# RP_ComputeModule3_rev_3_0_Displays.net
KiCad netlist of a schematic drawn in Altium Designer
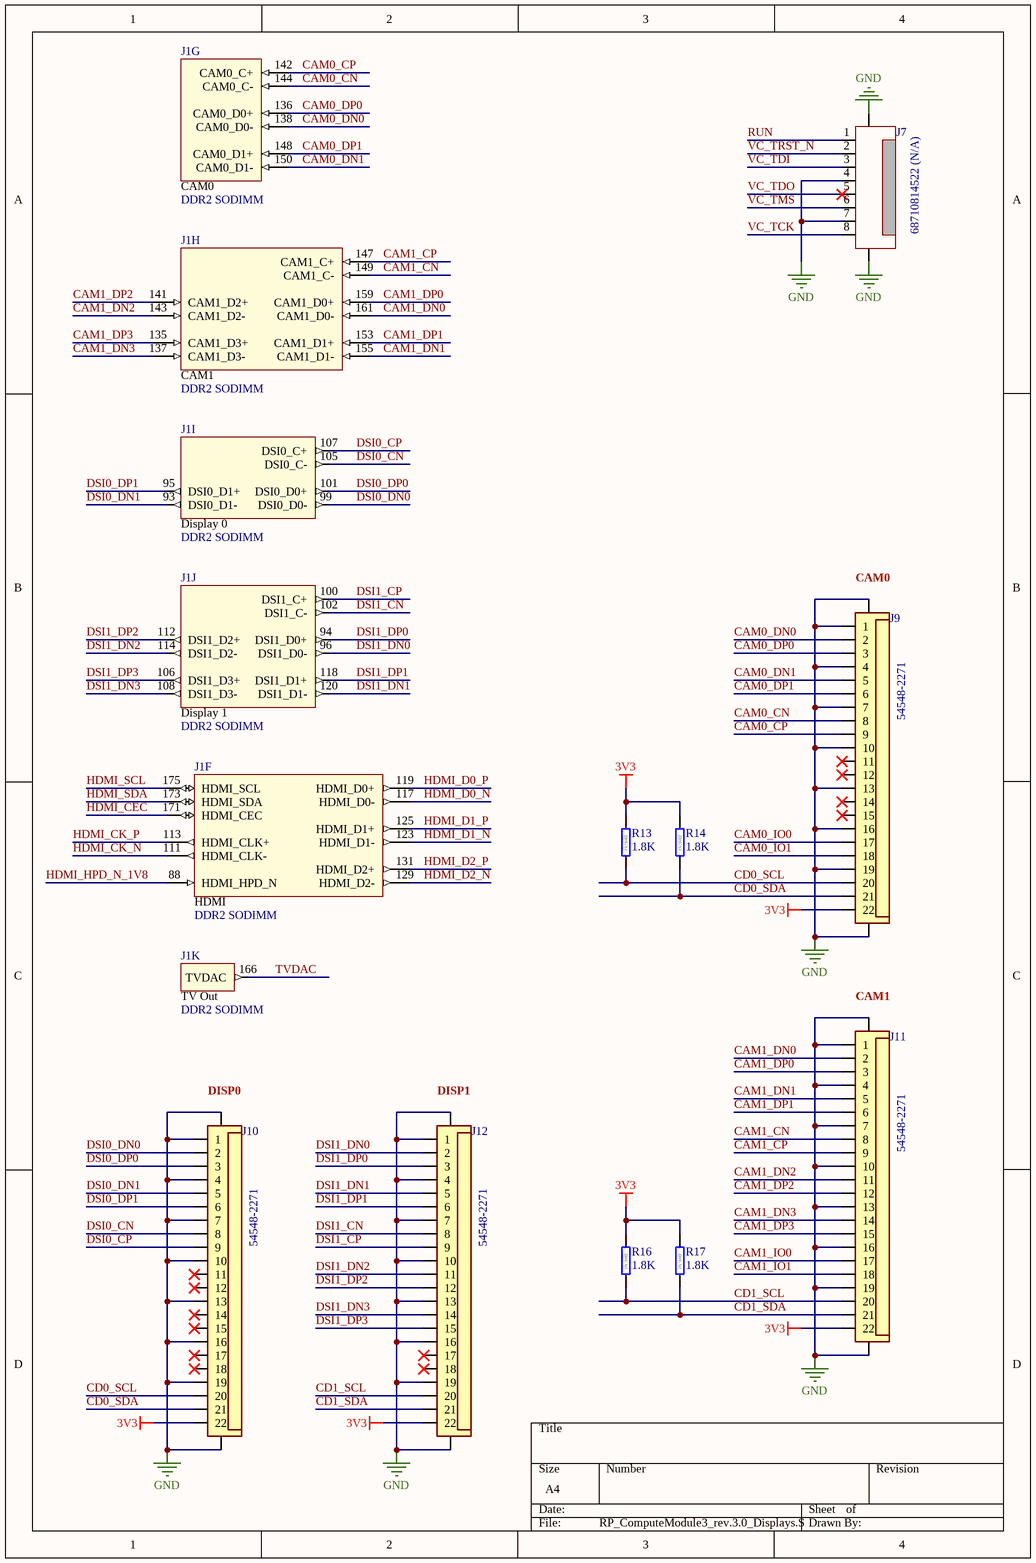
[diagram p0: RP_ComputeModule3_rev.3.0_Displays.SchDoc]

(export (version "E")
  (design (tool "Eeschema 10.0.6"))
  (components
    (comp (ref "J1")
      (value "DDR2 SODIMM")
      (footprint "TE 1473005-4 (DDR2 SO-DIMM)")
      (description "TE CONNECTIVITY / AMP         1473005-4             SOCKET IC, DIMM, DDR2, 1.8V, 200WAY")
      (fields
        (field (name "MANUFACTURER") "TE Connectivity")
        (field (name "MANUFACTURER PART NUMBER") "1473005-4")
      )
      (libsource (lib "TEConnectivity_AMP") (part "1473005-4"))
    )
    (comp (ref "J7")
      (value "68710814522 (N/A)")
      (footprint "WE 68710814522 N/A")
      (description "CONN FPC BOTTOM 8POS 0.50MM R/A")
      (fields
        (field (name "MANUFACTURER") "Wurth Electronics")
        (field (name "MANUFACTURER PART NUMBER") "68710814522")
      )
      (libsource (lib "WE_Library") (part "68710814522_N/A"))
    )
    (comp (ref "J9")
      (value "54548-2271")
      (footprint "Molex 54548-2271")
      (description "Conn FFC/FPC Connector SKT 22 POS 0.5mm Solder RA SMD Easy-On™ T/R")
      (fields (field (name "MANUFACTURER") "Molex") (field (name "MANUFACTURER PART NUMBER") "0545482271"))
      (libsource (lib "Molex_Library") (part "0545482271"))
    )
    (comp (ref "J10")
      (value "54548-2271")
      (footprint "Molex 54548-2271")
      (description "Conn FFC/FPC Connector SKT 22 POS 0.5mm Solder RA SMD Easy-On™ T/R")
      (fields (field (name "MANUFACTURER") "Molex") (field (name "MANUFACTURER PART NUMBER") "0545482271"))
      (libsource (lib "Molex_Library") (part "0545482271"))
    )
    (comp (ref "J11")
      (value "54548-2271")
      (footprint "Molex 54548-2271")
      (description "Conn FFC/FPC Connector SKT 22 POS 0.5mm Solder RA SMD Easy-On™ T/R")
      (fields (field (name "MANUFACTURER") "Molex") (field (name "MANUFACTURER PART NUMBER") "0545482271"))
      (libsource (lib "Molex_Library") (part "0545482271"))
    )
    (comp (ref "J12")
      (value "54548-2271")
      (footprint "Molex 54548-2271")
      (description "Conn FFC/FPC Connector SKT 22 POS 0.5mm Solder RA SMD Easy-On™ T/R")
      (fields (field (name "MANUFACTURER") "Molex") (field (name "MANUFACTURER PART NUMBER") "0545482271"))
      (libsource (lib "Molex_Library") (part "0545482271"))
    )
    (comp (ref "R13")
      (value "1.8K")
      (footprint "RES0402")
      (description "Thick Film Resistors - SMD 1.8K OHM 1%")
      (fields
        (field (name "MANUFACTURER") "KOA Speer")
        (field (name "MANUFACTURER PART NUMBER") "RK73H1ETTP1801F")
      )
      (libsource (lib "KOA_Resistors") (part "RK73H1ETTP1801F"))
    )
    (comp (ref "R14")
      (value "1.8K")
      (footprint "RES0402")
      (description "Thick Film Resistors - SMD 1.8K OHM 1%")
      (fields
        (field (name "MANUFACTURER") "KOA Speer")
        (field (name "MANUFACTURER PART NUMBER") "RK73H1ETTP1801F")
      )
      (libsource (lib "KOA_Resistors") (part "RK73H1ETTP1801F"))
    )
    (comp (ref "R16")
      (value "1.8K")
      (footprint "RES0402")
      (description "Thick Film Resistors - SMD 1.8K OHM 1%")
      (fields
        (field (name "MANUFACTURER") "KOA Speer")
        (field (name "MANUFACTURER PART NUMBER") "RK73H1ETTP1801F")
      )
      (libsource (lib "KOA_Resistors") (part "RK73H1ETTP1801F"))
    )
    (comp (ref "R17")
      (value "1.8K")
      (footprint "RES0402")
      (description "Thick Film Resistors - SMD 1.8K OHM 1%")
      (fields
        (field (name "MANUFACTURER") "KOA Speer")
        (field (name "MANUFACTURER PART NUMBER") "RK73H1ETTP1801F")
      )
      (libsource (lib "KOA_Resistors") (part "RK73H1ETTP1801F"))
    )
  )
  (nets
    (net (code "1") (name "/CAM0_CN") (class "Default")
      (node (ref "J1") (pin "144") (pinfunction "CAM0_C-_144") (pintype "input"))
      (node (ref "J9") (pin "8") (pinfunction "8_8") (pintype "passive"))
    )
    (net (code "2") (name "/CAM0_CP") (class "Default")
      (node (ref "J1") (pin "142") (pinfunction "CAM0_C+_142") (pintype "input"))
      (node (ref "J9") (pin "9") (pinfunction "9_9") (pintype "passive"))
    )
    (net (code "3") (name "/CAM0_DN0") (class "Default")
      (node (ref "J1") (pin "138") (pinfunction "CAM0_D0-_138") (pintype "input"))
      (node (ref "J9") (pin "2") (pinfunction "2_2") (pintype "passive"))
    )
    (net (code "4") (name "/CAM0_DN1") (class "Default")
      (node (ref "J1") (pin "150") (pinfunction "CAM0_D1-_150") (pintype "input"))
      (node (ref "J9") (pin "5") (pinfunction "5_5") (pintype "passive"))
    )
    (net (code "5") (name "/CAM0_DP0") (class "Default")
      (node (ref "J1") (pin "136") (pinfunction "CAM0_D0+_136") (pintype "input"))
      (node (ref "J9") (pin "3") (pinfunction "3_3") (pintype "passive"))
    )
    (net (code "6") (name "/CAM0_DP1") (class "Default")
      (node (ref "J1") (pin "148") (pinfunction "CAM0_D1+_148") (pintype "input"))
      (node (ref "J9") (pin "6") (pinfunction "6_6") (pintype "passive"))
    )
    (net (code "7") (name "/CAM0_IO0") (class "Default")
      (node (ref "J9") (pin "17") (pinfunction "17_17") (pintype "passive"))
    )
    (net (code "8") (name "/CAM0_IO1") (class "Default")
      (node (ref "J9") (pin "18") (pinfunction "18_18") (pintype "passive"))
    )
    (net (code "9") (name "/CAM1_CN") (class "Default")
      (node (ref "J1") (pin "149") (pinfunction "CAM1_C-_149") (pintype "input"))
      (node (ref "J11") (pin "8") (pinfunction "8_8") (pintype "passive"))
    )
    (net (code "10") (name "/CAM1_CP") (class "Default")
      (node (ref "J1") (pin "147") (pinfunction "CAM1_C+_147") (pintype "input"))
      (node (ref "J11") (pin "9") (pinfunction "9_9") (pintype "passive"))
    )
    (net (code "11") (name "/CAM1_DN0") (class "Default")
      (node (ref "J1") (pin "161") (pinfunction "CAM1_D0-_161") (pintype "input"))
      (node (ref "J11") (pin "2") (pinfunction "2_2") (pintype "passive"))
    )
    (net (code "12") (name "/CAM1_DN1") (class "Default")
      (node (ref "J1") (pin "155") (pinfunction "CAM1_D1-_155") (pintype "input"))
      (node (ref "J11") (pin "5") (pinfunction "5_5") (pintype "passive"))
    )
    (net (code "13") (name "/CAM1_DN2") (class "Default")
      (node (ref "J1") (pin "143") (pinfunction "CAM1_D2-_143") (pintype "input"))
      (node (ref "J11") (pin "11") (pinfunction "11_11") (pintype "passive"))
    )
    (net (code "14") (name "/CAM1_DN3") (class "Default")
      (node (ref "J1") (pin "137") (pinfunction "CAM1_D3-_137") (pintype "input"))
      (node (ref "J11") (pin "14") (pinfunction "14_14") (pintype "passive"))
    )
    (net (code "15") (name "/CAM1_DP0") (class "Default")
      (node (ref "J1") (pin "159") (pinfunction "CAM1_D0+_159") (pintype "input"))
      (node (ref "J11") (pin "3") (pinfunction "3_3") (pintype "passive"))
    )
    (net (code "16") (name "/CAM1_DP1") (class "Default")
      (node (ref "J1") (pin "153") (pinfunction "CAM1_D1+_153") (pintype "input"))
      (node (ref "J11") (pin "6") (pinfunction "6_6") (pintype "passive"))
    )
    (net (code "17") (name "/CAM1_DP2") (class "Default")
      (node (ref "J1") (pin "141") (pinfunction "CAM1_D2+_141") (pintype "input"))
      (node (ref "J11") (pin "12") (pinfunction "12_12") (pintype "passive"))
    )
    (net (code "18") (name "/CAM1_DP3") (class "Default")
      (node (ref "J1") (pin "135") (pinfunction "CAM1_D3+_135") (pintype "input"))
      (node (ref "J11") (pin "15") (pinfunction "15_15") (pintype "passive"))
    )
    (net (code "19") (name "/CAM1_IO0") (class "Default")
      (node (ref "J11") (pin "17") (pinfunction "17_17") (pintype "passive"))
    )
    (net (code "20") (name "/CAM1_IO1") (class "Default")
      (node (ref "J11") (pin "18") (pinfunction "18_18") (pintype "passive"))
    )
    (net (code "21") (name "/CD0_SCL") (class "Default")
      (node (ref "J10") (pin "20") (pinfunction "20_20") (pintype "passive"))
      (node (ref "J9") (pin "20") (pinfunction "20_20") (pintype "passive"))
      (node (ref "R13") (pin "2") (pinfunction "2_2") (pintype "passive"))
    )
    (net (code "22") (name "/CD0_SDA") (class "Default")
      (node (ref "J10") (pin "21") (pinfunction "21_21") (pintype "passive"))
      (node (ref "J9") (pin "21") (pinfunction "21_21") (pintype "passive"))
      (node (ref "R14") (pin "2") (pinfunction "2_2") (pintype "passive"))
    )
    (net (code "23") (name "/CD1_SCL") (class "Default")
      (node (ref "J11") (pin "20") (pinfunction "20_20") (pintype "passive"))
      (node (ref "J12") (pin "20") (pinfunction "20_20") (pintype "passive"))
      (node (ref "R16") (pin "2") (pinfunction "2_2") (pintype "passive"))
    )
    (net (code "24") (name "/CD1_SDA") (class "Default")
      (node (ref "J11") (pin "21") (pinfunction "21_21") (pintype "passive"))
      (node (ref "J12") (pin "21") (pinfunction "21_21") (pintype "passive"))
      (node (ref "R17") (pin "2") (pinfunction "2_2") (pintype "passive"))
    )
    (net (code "25") (name "/DSI0_CN") (class "Default")
      (node (ref "J1") (pin "105") (pinfunction "DSI0_C-_105") (pintype "output"))
      (node (ref "J10") (pin "8") (pinfunction "8_8") (pintype "passive"))
    )
    (net (code "26") (name "/DSI0_CP") (class "Default")
      (node (ref "J1") (pin "107") (pinfunction "DSI0_C+_107") (pintype "output"))
      (node (ref "J10") (pin "9") (pinfunction "9_9") (pintype "passive"))
    )
    (net (code "27") (name "/DSI0_DN0") (class "Default")
      (node (ref "J1") (pin "99") (pinfunction "DSI0_D0-_99") (pintype "output"))
      (node (ref "J10") (pin "2") (pinfunction "2_2") (pintype "passive"))
    )
    (net (code "28") (name "/DSI0_DN1") (class "Default")
      (node (ref "J1") (pin "93") (pinfunction "DSI0_D1-_93") (pintype "output"))
      (node (ref "J10") (pin "5") (pinfunction "5_5") (pintype "passive"))
    )
    (net (code "29") (name "/DSI0_DP0") (class "Default")
      (node (ref "J1") (pin "101") (pinfunction "DSI0_D0+_101") (pintype "output"))
      (node (ref "J10") (pin "3") (pinfunction "3_3") (pintype "passive"))
    )
    (net (code "30") (name "/DSI0_DP1") (class "Default")
      (node (ref "J1") (pin "95") (pinfunction "DSI0_D1+_95") (pintype "output"))
      (node (ref "J10") (pin "6") (pinfunction "6_6") (pintype "passive"))
    )
    (net (code "31") (name "/DSI1_CN") (class "Default")
      (node (ref "J1") (pin "102") (pinfunction "DSI1_C-_102") (pintype "output"))
      (node (ref "J12") (pin "8") (pinfunction "8_8") (pintype "passive"))
    )
    (net (code "32") (name "/DSI1_CP") (class "Default")
      (node (ref "J1") (pin "100") (pinfunction "DSI1_C+_100") (pintype "output"))
      (node (ref "J12") (pin "9") (pinfunction "9_9") (pintype "passive"))
    )
    (net (code "33") (name "/DSI1_DN0") (class "Default")
      (node (ref "J1") (pin "96") (pinfunction "DSI1_D0-_96") (pintype "output"))
      (node (ref "J12") (pin "2") (pinfunction "2_2") (pintype "passive"))
    )
    (net (code "34") (name "/DSI1_DN1") (class "Default")
      (node (ref "J1") (pin "120") (pinfunction "DSI1_D1-_120") (pintype "output"))
      (node (ref "J12") (pin "5") (pinfunction "5_5") (pintype "passive"))
    )
    (net (code "35") (name "/DSI1_DN2") (class "Default")
      (node (ref "J1") (pin "114") (pinfunction "DSI1_D2-_114") (pintype "output"))
      (node (ref "J12") (pin "11") (pinfunction "11_11") (pintype "passive"))
    )
    (net (code "36") (name "/DSI1_DN3") (class "Default")
      (node (ref "J1") (pin "108") (pinfunction "DSI1_D3-_108") (pintype "output"))
      (node (ref "J12") (pin "14") (pinfunction "14_14") (pintype "passive"))
    )
    (net (code "37") (name "/DSI1_DP0") (class "Default")
      (node (ref "J1") (pin "94") (pinfunction "DSI1_D0+_94") (pintype "output"))
      (node (ref "J12") (pin "3") (pinfunction "3_3") (pintype "passive"))
    )
    (net (code "38") (name "/DSI1_DP1") (class "Default")
      (node (ref "J1") (pin "118") (pinfunction "DSI1_D1+_118") (pintype "output"))
      (node (ref "J12") (pin "6") (pinfunction "6_6") (pintype "passive"))
    )
    (net (code "39") (name "/DSI1_DP2") (class "Default")
      (node (ref "J1") (pin "112") (pinfunction "DSI1_D2+_112") (pintype "output"))
      (node (ref "J12") (pin "12") (pinfunction "12_12") (pintype "passive"))
    )
    (net (code "40") (name "/DSI1_DP3") (class "Default")
      (node (ref "J1") (pin "106") (pinfunction "DSI1_D3+_106") (pintype "output"))
      (node (ref "J12") (pin "15") (pinfunction "15_15") (pintype "passive"))
    )
    (net (code "41") (name "/HDMI_CEC") (class "Default")
      (node (ref "J1") (pin "171") (pinfunction "HDMI_CEC_171") (pintype "bidirectional"))
    )
    (net (code "42") (name "/HDMI_CK_N") (class "Default")
      (node (ref "J1") (pin "111") (pinfunction "HDMI_CLK-_111") (pintype "output"))
    )
    (net (code "43") (name "/HDMI_CK_P") (class "Default")
      (node (ref "J1") (pin "113") (pinfunction "HDMI_CLK+_113") (pintype "output"))
    )
    (net (code "44") (name "/HDMI_D0_N") (class "Default")
      (node (ref "J1") (pin "117") (pinfunction "HDMI_D0-_117") (pintype "output"))
    )
    (net (code "45") (name "/HDMI_D0_P") (class "Default")
      (node (ref "J1") (pin "119") (pinfunction "HDMI_D0+_119") (pintype "output"))
    )
    (net (code "46") (name "/HDMI_D1_N") (class "Default")
      (node (ref "J1") (pin "123") (pinfunction "HDMI_D1-_123") (pintype "output"))
    )
    (net (code "47") (name "/HDMI_D1_P") (class "Default")
      (node (ref "J1") (pin "125") (pinfunction "HDMI_D1+_125") (pintype "output"))
    )
    (net (code "48") (name "/HDMI_D2_N") (class "Default")
      (node (ref "J1") (pin "129") (pinfunction "HDMI_D2-_129") (pintype "output"))
    )
    (net (code "49") (name "/HDMI_D2_P") (class "Default")
      (node (ref "J1") (pin "131") (pinfunction "HDMI_D2+_131") (pintype "output"))
    )
    (net (code "50") (name "/HDMI_HPD_N_1V8") (class "Default")
      (node (ref "J1") (pin "88") (pinfunction "HDMI_HPD_N_88") (pintype "input"))
    )
    (net (code "51") (name "/HDMI_SCL") (class "Default")
      (node (ref "J1") (pin "175") (pinfunction "HDMI_SCL_175") (pintype "bidirectional"))
    )
    (net (code "52") (name "/HDMI_SDA") (class "Default")
      (node (ref "J1") (pin "173") (pinfunction "HDMI_SDA_173") (pintype "bidirectional"))
    )
    (net (code "53") (name "/RUN") (class "Default")
      (node (ref "J7") (pin "1") (pinfunction "1_1") (pintype "passive"))
    )
    (net (code "54") (name "/TVDAC") (class "Default")
      (node (ref "J1") (pin "166") (pinfunction "TVDAC_166") (pintype "output"))
    )
    (net (code "55") (name "/VC_TCK") (class "Default")
      (node (ref "J7") (pin "8") (pinfunction "8_8") (pintype "passive"))
    )
    (net (code "56") (name "/VC_TDI") (class "Default")
      (node (ref "J7") (pin "3") (pinfunction "3_3") (pintype "passive"))
    )
    (net (code "57") (name "/VC_TDO") (class "Default")
      (node (ref "J7") (pin "5") (pinfunction "5_5") (pintype "passive+no_connect"))
    )
    (net (code "58") (name "/VC_TMS") (class "Default")
      (node (ref "J7") (pin "6") (pinfunction "6_6") (pintype "passive"))
    )
    (net (code "59") (name "/VC_TRST_N") (class "Default")
      (node (ref "J7") (pin "2") (pinfunction "2_2") (pintype "passive"))
    )
    (net (code "60") (name "3V3") (class "Default")
      (node (ref "J10") (pin "22") (pinfunction "22_22") (pintype "passive"))
      (node (ref "J11") (pin "22") (pinfunction "22_22") (pintype "passive"))
      (node (ref "J12") (pin "22") (pinfunction "22_22") (pintype "passive"))
      (node (ref "J9") (pin "22") (pinfunction "22_22") (pintype "passive"))
      (node (ref "R13") (pin "1") (pinfunction "1_1") (pintype "passive"))
      (node (ref "R14") (pin "1") (pinfunction "1_1") (pintype "passive"))
      (node (ref "R16") (pin "1") (pinfunction "1_1") (pintype "passive"))
      (node (ref "R17") (pin "1") (pinfunction "1_1") (pintype "passive"))
    )
    (net (code "61") (name "GND") (class "Default")
      (node (ref "J10") (pin "1") (pinfunction "1_1") (pintype "passive"))
      (node (ref "J10") (pin "10") (pinfunction "10_10") (pintype "passive"))
      (node (ref "J10") (pin "13") (pinfunction "13_13") (pintype "passive"))
      (node (ref "J10") (pin "16") (pinfunction "16_16") (pintype "passive"))
      (node (ref "J10") (pin "19") (pinfunction "19_19") (pintype "passive"))
      (node (ref "J10") (pin "4") (pinfunction "4_4") (pintype "passive"))
      (node (ref "J10") (pin "7") (pinfunction "7_7") (pintype "passive"))
      (node (ref "J10") (pin "G1") (pinfunction "G1_G1") (pintype "passive"))
      (node (ref "J10") (pin "G2") (pinfunction "G2_G2") (pintype "passive"))
      (node (ref "J11") (pin "1") (pinfunction "1_1") (pintype "passive"))
      (node (ref "J11") (pin "10") (pinfunction "10_10") (pintype "passive"))
      (node (ref "J11") (pin "13") (pinfunction "13_13") (pintype "passive"))
      (node (ref "J11") (pin "16") (pinfunction "16_16") (pintype "passive"))
      (node (ref "J11") (pin "19") (pinfunction "19_19") (pintype "passive"))
      (node (ref "J11") (pin "4") (pinfunction "4_4") (pintype "passive"))
      (node (ref "J11") (pin "7") (pinfunction "7_7") (pintype "passive"))
      (node (ref "J11") (pin "G1") (pinfunction "G1_G1") (pintype "passive"))
      (node (ref "J11") (pin "G2") (pinfunction "G2_G2") (pintype "passive"))
      (node (ref "J12") (pin "1") (pinfunction "1_1") (pintype "passive"))
      (node (ref "J12") (pin "10") (pinfunction "10_10") (pintype "passive"))
      (node (ref "J12") (pin "13") (pinfunction "13_13") (pintype "passive"))
      (node (ref "J12") (pin "16") (pinfunction "16_16") (pintype "passive"))
      (node (ref "J12") (pin "19") (pinfunction "19_19") (pintype "passive"))
      (node (ref "J12") (pin "4") (pinfunction "4_4") (pintype "passive"))
      (node (ref "J12") (pin "7") (pinfunction "7_7") (pintype "passive"))
      (node (ref "J12") (pin "G1") (pinfunction "G1_G1") (pintype "passive"))
      (node (ref "J12") (pin "G2") (pinfunction "G2_G2") (pintype "passive"))
      (node (ref "J7") (pin "10") (pinfunction "10_10") (pintype "passive"))
      (node (ref "J7") (pin "4") (pinfunction "4_4") (pintype "passive"))
      (node (ref "J7") (pin "7") (pinfunction "7_7") (pintype "passive"))
      (node (ref "J7") (pin "9") (pinfunction "9_9") (pintype "passive"))
      (node (ref "J9") (pin "1") (pinfunction "1_1") (pintype "passive"))
      (node (ref "J9") (pin "10") (pinfunction "10_10") (pintype "passive"))
      (node (ref "J9") (pin "13") (pinfunction "13_13") (pintype "passive"))
      (node (ref "J9") (pin "16") (pinfunction "16_16") (pintype "passive"))
      (node (ref "J9") (pin "19") (pinfunction "19_19") (pintype "passive"))
      (node (ref "J9") (pin "4") (pinfunction "4_4") (pintype "passive"))
      (node (ref "J9") (pin "7") (pinfunction "7_7") (pintype "passive"))
      (node (ref "J9") (pin "G1") (pinfunction "G1_G1") (pintype "passive"))
      (node (ref "J9") (pin "G2") (pinfunction "G2_G2") (pintype "passive"))
    )
    (net (code "62") (name "unconnected-(J9-Pad11)") (class "Default")
      (node (ref "J9") (pin "11") (pinfunction "11_11") (pintype "passive+no_connect"))
    )
    (net (code "63") (name "unconnected-(J9-Pad12)") (class "Default")
      (node (ref "J9") (pin "12") (pinfunction "12_12") (pintype "passive+no_connect"))
    )
    (net (code "64") (name "unconnected-(J9-Pad14)") (class "Default")
      (node (ref "J9") (pin "14") (pinfunction "14_14") (pintype "passive+no_connect"))
    )
    (net (code "65") (name "unconnected-(J9-Pad15)") (class "Default")
      (node (ref "J9") (pin "15") (pinfunction "15_15") (pintype "passive+no_connect"))
    )
    (net (code "66") (name "unconnected-(J10-Pad11)") (class "Default")
      (node (ref "J10") (pin "11") (pinfunction "11_11") (pintype "passive+no_connect"))
    )
    (net (code "67") (name "unconnected-(J10-Pad12)") (class "Default")
      (node (ref "J10") (pin "12") (pinfunction "12_12") (pintype "passive+no_connect"))
    )
    (net (code "68") (name "unconnected-(J10-Pad14)") (class "Default")
      (node (ref "J10") (pin "14") (pinfunction "14_14") (pintype "passive+no_connect"))
    )
    (net (code "69") (name "unconnected-(J10-Pad15)") (class "Default")
      (node (ref "J10") (pin "15") (pinfunction "15_15") (pintype "passive+no_connect"))
    )
    (net (code "70") (name "unconnected-(J10-Pad17)") (class "Default")
      (node (ref "J10") (pin "17") (pinfunction "17_17") (pintype "passive+no_connect"))
    )
    (net (code "71") (name "unconnected-(J10-Pad18)") (class "Default")
      (node (ref "J10") (pin "18") (pinfunction "18_18") (pintype "passive+no_connect"))
    )
    (net (code "72") (name "unconnected-(J12-Pad17)") (class "Default")
      (node (ref "J12") (pin "17") (pinfunction "17_17") (pintype "passive+no_connect"))
    )
    (net (code "73") (name "unconnected-(J12-Pad18)") (class "Default")
      (node (ref "J12") (pin "18") (pinfunction "18_18") (pintype "passive+no_connect"))
    )
  )
)
